# OR.net
KiCad netlist of a schematic drawn in EAGLE
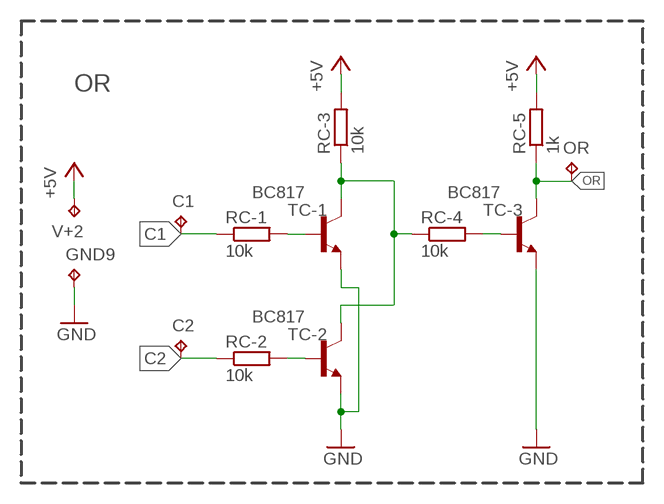
[diagram p0: schematic, sheet 1]

(export (version "E")
  (design (tool "Eeschema 10.0.6"))
  (components
    (comp (ref "C1")
      (value "TPTP07R")
      (footprint "eagle-import:TP07R")
      (libsource (lib "eagle-import") (part "TPTP07R"))
    )
    (comp (ref "C2")
      (value "TPTP07R")
      (footprint "eagle-import:TP07R")
      (libsource (lib "eagle-import") (part "TPTP07R"))
    )
    (comp (ref "GND9")
      (value "TPTP07R")
      (footprint "eagle-import:TP07R")
      (libsource (lib "eagle-import") (part "TPTP07R"))
    )
    (comp (ref "OR")
      (value "TPTP07R")
      (footprint "eagle-import:TP07R")
      (libsource (lib "eagle-import") (part "TPTP07R"))
    )
    (comp (ref "RC-1")
      (value "10k")
      (footprint "eagle-import:R0603")
      (libsource (lib "eagle-import") (part "R-EU_R0603"))
    )
    (comp (ref "RC-2")
      (value "10k")
      (footprint "eagle-import:R0603")
      (libsource (lib "eagle-import") (part "R-EU_R0603"))
    )
    (comp (ref "RC-3")
      (value "10k")
      (footprint "eagle-import:R0603")
      (libsource (lib "eagle-import") (part "R-EU_R0603"))
    )
    (comp (ref "RC-4")
      (value "10k")
      (footprint "eagle-import:R0603")
      (libsource (lib "eagle-import") (part "R-EU_R0603"))
    )
    (comp (ref "RC-5")
      (value "1k")
      (footprint "eagle-import:R0603")
      (libsource (lib "eagle-import") (part "R-EU_R0603"))
    )
    (comp (ref "TC-1")
      (value "BC817")
      (footprint "eagle-import:SOT23-BEC")
      (libsource (lib "eagle-import") (part "-NPN-SOT23-BECBC817-40"))
    )
    (comp (ref "TC-2")
      (value "BC817")
      (footprint "eagle-import:SOT23-BEC")
      (libsource (lib "eagle-import") (part "-NPN-SOT23-BECBC817-40"))
    )
    (comp (ref "TC-3")
      (value "BC817")
      (footprint "eagle-import:SOT23-BEC")
      (libsource (lib "eagle-import") (part "-NPN-SOT23-BECBC817-40"))
    )
    (comp (ref "V+2")
      (value "TPTP07R")
      (footprint "eagle-import:TP07R")
      (libsource (lib "eagle-import") (part "TPTP07R"))
    )
  )
  (nets
    (net (code "1") (name "+5V") (class "Default")
      (node (ref "RC-3") (pin "2") (pinfunction "2_2") (pintype "passive"))
      (node (ref "RC-5") (pin "2") (pinfunction "2_2") (pintype "passive"))
      (node (ref "V+2") (pin "TP") (pinfunction "TP_TP") (pintype "input"))
    )
    (net (code "2") (name "C1") (class "Default")
      (node (ref "C1") (pin "TP") (pinfunction "TP_TP") (pintype "input"))
      (node (ref "RC-1") (pin "1") (pinfunction "1_1") (pintype "passive"))
    )
    (net (code "3") (name "C2") (class "Default")
      (node (ref "C2") (pin "TP") (pinfunction "TP_TP") (pintype "input"))
      (node (ref "RC-2") (pin "1") (pinfunction "1_1") (pintype "passive"))
    )
    (net (code "4") (name "GND") (class "Default")
      (node (ref "GND9") (pin "TP") (pinfunction "TP_TP") (pintype "input"))
      (node (ref "TC-1") (pin "E") (pinfunction "E_E") (pintype "passive"))
      (node (ref "TC-2") (pin "E") (pinfunction "E_E") (pintype "passive"))
      (node (ref "TC-3") (pin "E") (pinfunction "E_E") (pintype "passive"))
    )
    (net (code "5") (name "Net-(RC-1-Pad2)") (class "Default")
      (node (ref "RC-1") (pin "2") (pinfunction "2_2") (pintype "passive"))
      (node (ref "TC-1") (pin "B") (pinfunction "B_B") (pintype "passive"))
    )
    (net (code "6") (name "Net-(RC-2-Pad2)") (class "Default")
      (node (ref "RC-2") (pin "2") (pinfunction "2_2") (pintype "passive"))
      (node (ref "TC-2") (pin "B") (pinfunction "B_B") (pintype "passive"))
    )
    (net (code "7") (name "Net-(RC-3-Pad1)") (class "Default")
      (node (ref "RC-3") (pin "1") (pinfunction "1_1") (pintype "passive"))
      (node (ref "RC-4") (pin "1") (pinfunction "1_1") (pintype "passive"))
      (node (ref "TC-1") (pin "C") (pinfunction "C_C") (pintype "passive"))
      (node (ref "TC-2") (pin "C") (pinfunction "C_C") (pintype "passive"))
    )
    (net (code "8") (name "Net-(RC-4-Pad2)") (class "Default")
      (node (ref "RC-4") (pin "2") (pinfunction "2_2") (pintype "passive"))
      (node (ref "TC-3") (pin "B") (pinfunction "B_B") (pintype "passive"))
    )
    (net (code "9") (name "OR") (class "Default")
      (node (ref "OR") (pin "TP") (pinfunction "TP_TP") (pintype "input"))
      (node (ref "RC-5") (pin "1") (pinfunction "1_1") (pintype "passive"))
      (node (ref "TC-3") (pin "C") (pinfunction "C_C") (pintype "passive"))
    )
  )
)
